# communication_module_to_aj-doy.net
KiCad netlist of a schematic drawn in EAGLE
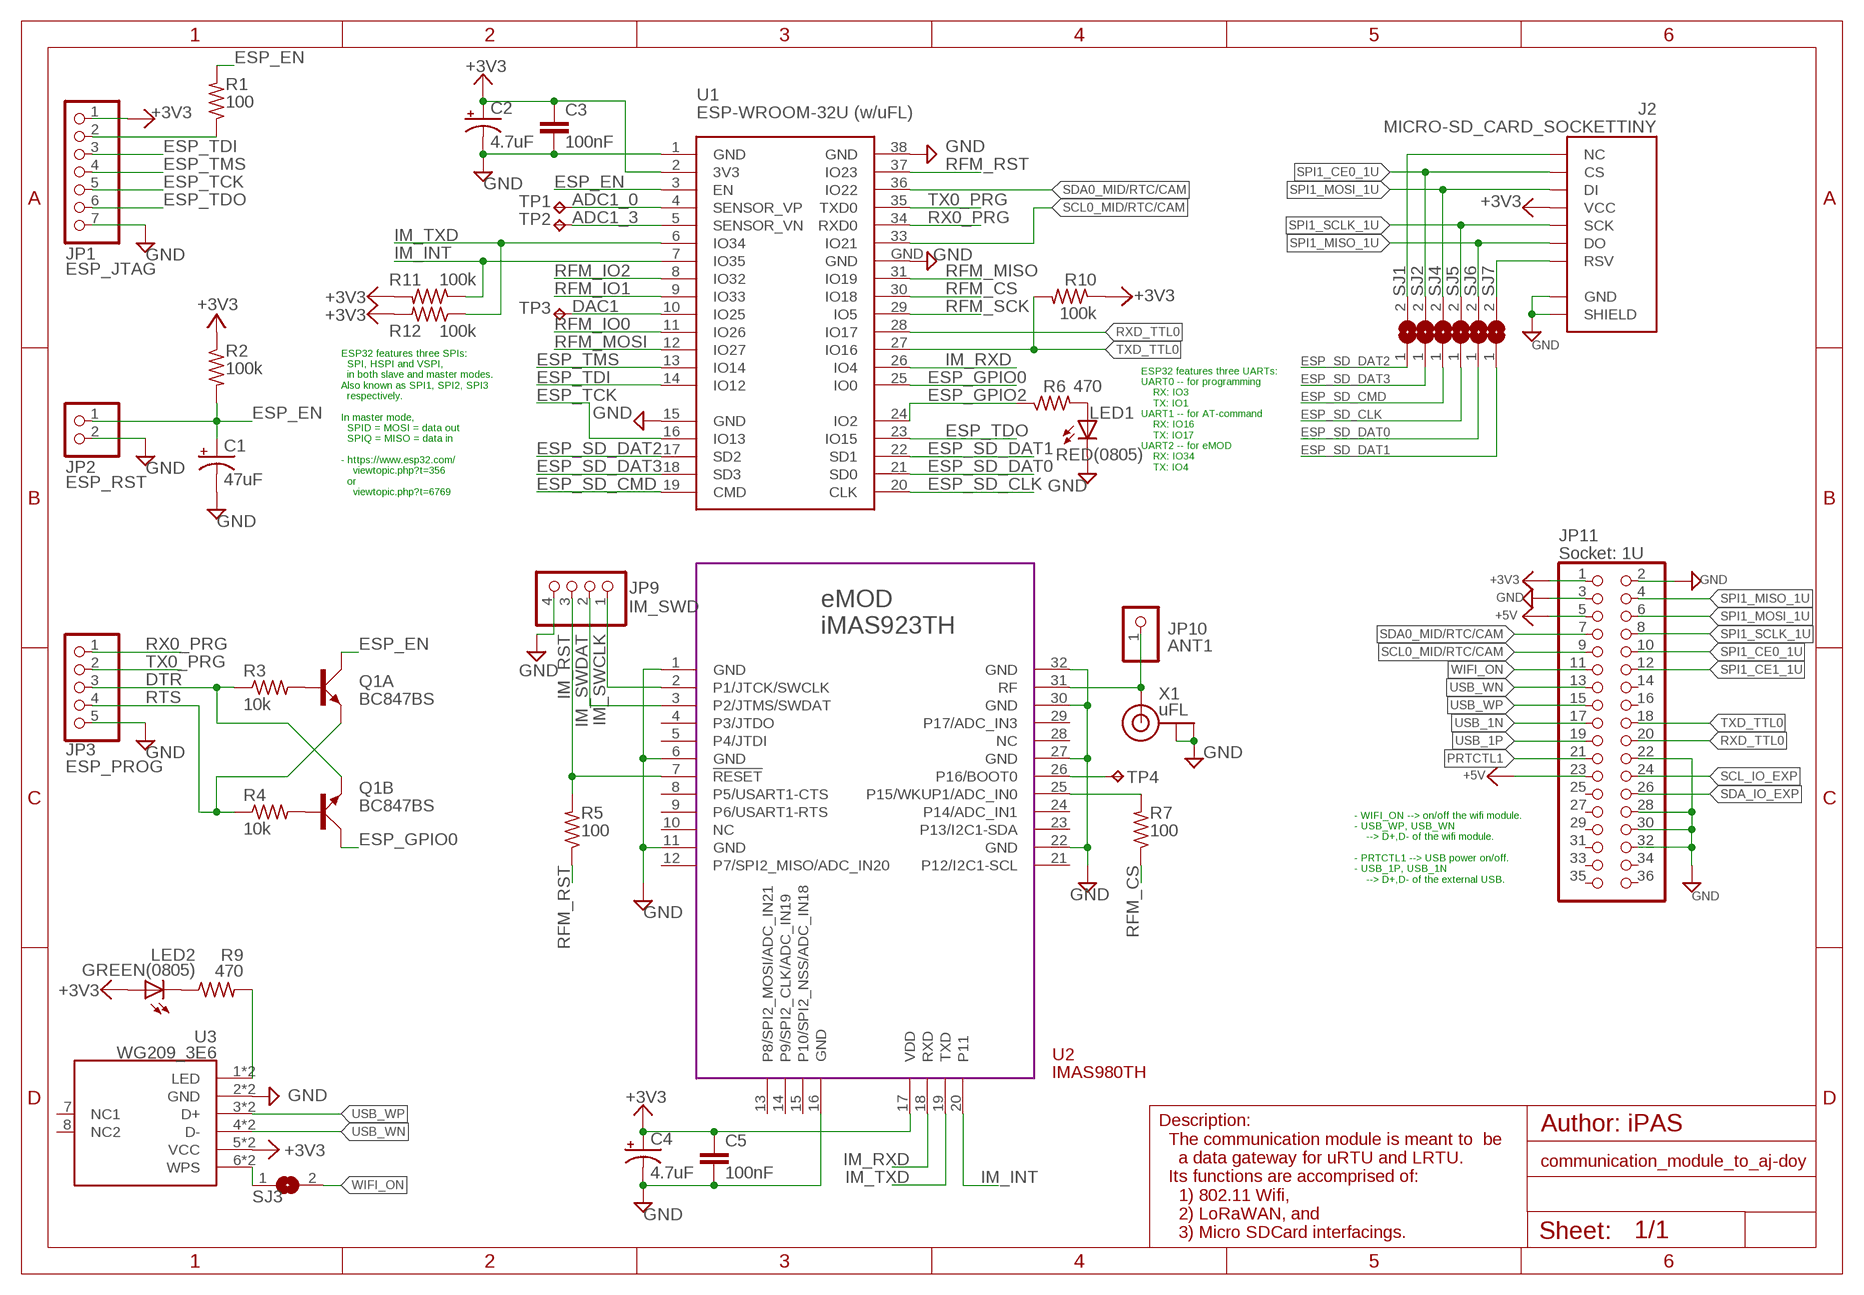
[diagram p0: schematic, sheet 1]

(export (version "E")
  (design (tool "Eeschema 10.0.6"))
  (components
    (comp (ref "C1")
      (value "47uF")
      (footprint "eagle-import:RCL_150CLZ-1014")
      (libsource (lib "eagle-import") (part "RCL_CPOL-US150CLZ-1014"))
    )
    (comp (ref "C2")
      (value "4.7uF")
      (footprint "eagle-import:RCL_150CLZ-1014")
      (libsource (lib "eagle-import") (part "RCL_CPOL-US150CLZ-1014"))
    )
    (comp (ref "C3")
      (value "100nF")
      (footprint "eagle-import:RCL_C1206")
      (libsource (lib "eagle-import") (part "RCL_C-EUC1206"))
    )
    (comp (ref "C4")
      (value "4.7uF")
      (footprint "eagle-import:RCL_150CLZ-1014")
      (libsource (lib "eagle-import") (part "RCL_CPOL-US150CLZ-1014"))
    )
    (comp (ref "C5")
      (value "100nF")
      (footprint "eagle-import:RCL_C1206")
      (libsource (lib "eagle-import") (part "RCL_C-EUC1206"))
    )
    (comp (ref "J2")
      (value "MICRO-SD_CARD_SOCKETTINY")
      (footprint "eagle-import:MICROSD_TINY")
      (libsource (lib "eagle-import") (part "MICRO-SD_CARD_SOCKETTINY"))
    )
    (comp (ref "JP1")
      (value "ESP_JTAG")
      (footprint "eagle-import:1X07")
      (libsource (lib "eagle-import") (part "PINHD-1X7"))
    )
    (comp (ref "JP2")
      (value "ESP_RST")
      (footprint "eagle-import:1X02")
      (libsource (lib "eagle-import") (part "PINHD-1X2"))
    )
    (comp (ref "JP3")
      (value "ESP_PROG")
      (footprint "eagle-import:1X05")
      (libsource (lib "eagle-import") (part "PINHD-1X5"))
    )
    (comp (ref "JP9")
      (value "IM_SWD")
      (footprint "eagle-import:1X04")
      (libsource (lib "eagle-import") (part "PINHD-1X4"))
    )
    (comp (ref "JP10")
      (value "ANT1")
      (footprint "eagle-import:1X01_ROUND")
      (libsource (lib "eagle-import") (part "HEADER-1X1ROUND"))
    )
    (comp (ref "JP11")
      (value "Socket: 1U")
      (footprint "eagle-import:2X18")
      (libsource (lib "eagle-import") (part "PINHD-2X18"))
    )
    (comp (ref "LED1")
      (value "RED(0805)")
      (footprint "eagle-import:CHIP-LED0805")
      (libsource (lib "eagle-import") (part "LEDCHIP-LED0805"))
    )
    (comp (ref "LED2")
      (value "GREEN(0805)")
      (footprint "eagle-import:CHIP-LED0805")
      (libsource (lib "eagle-import") (part "LEDCHIP-LED0805"))
    )
    (comp (ref "Q1")
      (value "BC847BS")
      (footprint "eagle-import:SOT363_PHILIPS")
      (libsource (lib "eagle-import") (part "BC847BS"))
    )
    (comp (ref "R1")
      (value "100")
      (footprint "eagle-import:RCL_M0805")
      (libsource (lib "eagle-import") (part "RCL_R-USM0805"))
    )
    (comp (ref "R2")
      (value "100k")
      (footprint "eagle-import:RCL_M0805")
      (libsource (lib "eagle-import") (part "RCL_R-USM0805"))
    )
    (comp (ref "R3")
      (value "10k")
      (footprint "eagle-import:RCL_M0805")
      (libsource (lib "eagle-import") (part "RCL_R-USM0805"))
    )
    (comp (ref "R4")
      (value "10k")
      (footprint "eagle-import:RCL_M0805")
      (libsource (lib "eagle-import") (part "RCL_R-USM0805"))
    )
    (comp (ref "R5")
      (value "100")
      (footprint "eagle-import:RCL_M0805")
      (libsource (lib "eagle-import") (part "RCL_R-USM0805"))
    )
    (comp (ref "R6")
      (value "470")
      (footprint "eagle-import:RCL_M0805")
      (libsource (lib "eagle-import") (part "RCL_R-USM0805"))
    )
    (comp (ref "R7")
      (value "100")
      (footprint "eagle-import:RCL_M0805")
      (libsource (lib "eagle-import") (part "RCL_R-USM0805"))
    )
    (comp (ref "R9")
      (value "470")
      (footprint "eagle-import:RCL_M0805")
      (libsource (lib "eagle-import") (part "RCL_R-USM0805"))
    )
    (comp (ref "R10")
      (value "100k")
      (footprint "eagle-import:RCL_M0805")
      (libsource (lib "eagle-import") (part "RCL_R-USM0805"))
    )
    (comp (ref "R11")
      (value "100k")
      (footprint "eagle-import:RCL_M0805")
      (libsource (lib "eagle-import") (part "RCL_R-USM0805"))
    )
    (comp (ref "R12")
      (value "100k")
      (footprint "eagle-import:RCL_M0805")
      (libsource (lib "eagle-import") (part "RCL_R-USM0805"))
    )
    (comp (ref "SJ1")
      (value "SOLDERJUMPERREFLOW")
      (footprint "eagle-import:SOLDERJUMPER_REFLOW")
      (libsource (lib "eagle-import") (part "SOLDERJUMPERREFLOW"))
    )
    (comp (ref "SJ2")
      (value "SOLDERJUMPERREFLOW")
      (footprint "eagle-import:SOLDERJUMPER_REFLOW")
      (libsource (lib "eagle-import") (part "SOLDERJUMPERREFLOW"))
    )
    (comp (ref "SJ3")
      (value "SOLDERJUMPERREFLOW")
      (footprint "eagle-import:SOLDERJUMPER_REFLOW")
      (libsource (lib "eagle-import") (part "SOLDERJUMPERREFLOW"))
    )
    (comp (ref "SJ4")
      (value "SOLDERJUMPERREFLOW")
      (footprint "eagle-import:SOLDERJUMPER_REFLOW")
      (libsource (lib "eagle-import") (part "SOLDERJUMPERREFLOW"))
    )
    (comp (ref "SJ5")
      (value "SOLDERJUMPERREFLOW")
      (footprint "eagle-import:SOLDERJUMPER_REFLOW")
      (libsource (lib "eagle-import") (part "SOLDERJUMPERREFLOW"))
    )
    (comp (ref "SJ6")
      (value "SOLDERJUMPERREFLOW")
      (footprint "eagle-import:SOLDERJUMPER_REFLOW")
      (libsource (lib "eagle-import") (part "SOLDERJUMPERREFLOW"))
    )
    (comp (ref "SJ7")
      (value "SOLDERJUMPERREFLOW")
      (footprint "eagle-import:SOLDERJUMPER_REFLOW")
      (libsource (lib "eagle-import") (part "SOLDERJUMPERREFLOW"))
    )
    (comp (ref "TP1")
      (value "TPB1,27")
      (footprint "eagle-import:B1,27")
      (libsource (lib "eagle-import") (part "TPB1,27"))
    )
    (comp (ref "TP2")
      (value "TPB1,27")
      (footprint "eagle-import:B1,27")
      (libsource (lib "eagle-import") (part "TPB1,27"))
    )
    (comp (ref "TP3")
      (value "TPB1,27")
      (footprint "eagle-import:B1,27")
      (libsource (lib "eagle-import") (part "TPB1,27"))
    )
    (comp (ref "TP4")
      (value "TPB1,27")
      (footprint "eagle-import:B1,27")
      (libsource (lib "eagle-import") (part "TPB1,27"))
    )
    (comp (ref "U1")
      (value "ESP-WROOM-32U (w/uFL)")
      (footprint "eagle-import:ESP-WROOM-32")
      (libsource (lib "eagle-import") (part "ESP-WROOM-32"))
    )
    (comp (ref "U2")
      (value "IMAS980TH")
      (footprint "eagle-import:IMAS923TH")
      (libsource (lib "eagle-import") (part "IMAS980TH"))
    )
    (comp (ref "U3")
      (value "WG209_3E6")
      (footprint "eagle-import:WG209")
      (libsource (lib "eagle-import") (part "WG209"))
    )
    (comp (ref "X1")
      (value "uFL")
      (footprint "eagle-import:U.FL")
      (libsource (lib "eagle-import") (part "ANTENNA_U.FL"))
    )
  )
  (nets
    (net (code "1") (name "+3V3") (class "Default")
      (node (ref "C2") (pin "+") (pinfunction "+_+") (pintype "passive"))
      (node (ref "C3") (pin "1") (pinfunction "1_1") (pintype "passive"))
      (node (ref "C4") (pin "+") (pinfunction "+_+") (pintype "passive"))
      (node (ref "C5") (pin "1") (pinfunction "1_1") (pintype "passive"))
      (node (ref "J2") (pin "4") (pinfunction "VCC_4") (pintype "bidirectional"))
      (node (ref "JP1") (pin "1") (pinfunction "1_1") (pintype "passive"))
      (node (ref "JP11") (pin "1") (pinfunction "1_1") (pintype "passive"))
      (node (ref "LED2") (pin "A") (pinfunction "A_A") (pintype "passive"))
      (node (ref "R10") (pin "1") (pinfunction "1_1") (pintype "passive"))
      (node (ref "R11") (pin "2") (pinfunction "2_2") (pintype "passive"))
      (node (ref "R12") (pin "2") (pinfunction "2_2") (pintype "passive"))
      (node (ref "R2") (pin "1") (pinfunction "1_1") (pintype "passive"))
      (node (ref "U1") (pin "2") (pinfunction "3V3_2") (pintype "power_in"))
      (node (ref "U2") (pin "17") (pinfunction "VDD_17") (pintype "power_in"))
      (node (ref "U3") (pin "5") (pinfunction "VCC_5") (pintype "power_in"))
      (node (ref "U3") (pin "5P") (pinfunction "VCC_5P") (pintype "power_in"))
    )
    (net (code "2") (name "+5V") (class "Default")
      (node (ref "JP11") (pin "23") (pinfunction "23_23") (pintype "passive"))
      (node (ref "JP11") (pin "5") (pinfunction "5_5") (pintype "passive"))
    )
    (net (code "3") (name "/ADC1_0") (class "Default")
      (node (ref "TP1") (pin "TP") (pinfunction "TP_TP") (pintype "input"))
      (node (ref "U1") (pin "4") (pinfunction "SENSOR_VP_4") (pintype "bidirectional"))
    )
    (net (code "4") (name "/ADC1_3") (class "Default")
      (node (ref "TP2") (pin "TP") (pinfunction "TP_TP") (pintype "input"))
      (node (ref "U1") (pin "5") (pinfunction "SENSOR_VN_5") (pintype "bidirectional"))
    )
    (net (code "5") (name "/DAC1") (class "Default")
      (node (ref "TP3") (pin "TP") (pinfunction "TP_TP") (pintype "input"))
      (node (ref "U1") (pin "10") (pinfunction "IO25_10") (pintype "bidirectional"))
    )
    (net (code "6") (name "/DTR") (class "Default")
      (node (ref "JP3") (pin "3") (pinfunction "3_3") (pintype "passive"))
      (node (ref "Q1") (pin "4") (pinfunction "E_4") (pintype "passive"))
      (node (ref "R3") (pin "1") (pinfunction "1_1") (pintype "passive"))
    )
    (net (code "7") (name "/ESP_EN") (class "Default")
      (node (ref "C1") (pin "+") (pinfunction "+_+") (pintype "passive"))
      (node (ref "JP2") (pin "1") (pinfunction "1_1") (pintype "passive"))
      (node (ref "Q1") (pin "6") (pinfunction "C_6") (pintype "passive"))
      (node (ref "R1") (pin "2") (pinfunction "2_2") (pintype "passive"))
      (node (ref "R2") (pin "2") (pinfunction "2_2") (pintype "passive"))
      (node (ref "U1") (pin "3") (pinfunction "EN_3") (pintype "input"))
    )
    (net (code "8") (name "/ESP_GPIO0") (class "Default")
      (node (ref "Q1") (pin "3") (pinfunction "C_3") (pintype "passive"))
      (node (ref "U1") (pin "25") (pinfunction "IO0_25") (pintype "bidirectional"))
    )
    (net (code "9") (name "/ESP_GPIO2") (class "Default")
      (node (ref "R6") (pin "1") (pinfunction "1_1") (pintype "passive"))
      (node (ref "U1") (pin "24") (pinfunction "IO2_24") (pintype "bidirectional"))
    )
    (net (code "10") (name "/ESP_SD_CLK") (class "Default")
      (node (ref "SJ5") (pin "1") (pinfunction "1_1") (pintype "passive"))
      (node (ref "U1") (pin "20") (pinfunction "CLK_20") (pintype "bidirectional"))
    )
    (net (code "11") (name "/ESP_SD_CMD") (class "Default")
      (node (ref "SJ4") (pin "1") (pinfunction "1_1") (pintype "passive"))
      (node (ref "U1") (pin "19") (pinfunction "CMD_19") (pintype "bidirectional"))
    )
    (net (code "12") (name "/ESP_SD_DAT0") (class "Default")
      (node (ref "SJ6") (pin "1") (pinfunction "1_1") (pintype "passive"))
      (node (ref "U1") (pin "21") (pinfunction "SD0_21") (pintype "bidirectional"))
    )
    (net (code "13") (name "/ESP_SD_DAT1") (class "Default")
      (node (ref "SJ7") (pin "1") (pinfunction "1_1") (pintype "passive"))
      (node (ref "U1") (pin "22") (pinfunction "SD1_22") (pintype "bidirectional"))
    )
    (net (code "14") (name "/ESP_SD_DAT2") (class "Default")
      (node (ref "SJ1") (pin "1") (pinfunction "1_1") (pintype "passive"))
      (node (ref "U1") (pin "17") (pinfunction "SD2_17") (pintype "bidirectional"))
    )
    (net (code "15") (name "/ESP_SD_DAT3") (class "Default")
      (node (ref "SJ2") (pin "1") (pinfunction "1_1") (pintype "passive"))
      (node (ref "U1") (pin "18") (pinfunction "SD3_18") (pintype "bidirectional"))
    )
    (net (code "16") (name "/ESP_TCK") (class "Default")
      (node (ref "JP1") (pin "5") (pinfunction "5_5") (pintype "passive"))
      (node (ref "U1") (pin "16") (pinfunction "IO13_16") (pintype "bidirectional"))
    )
    (net (code "17") (name "/ESP_TDI") (class "Default")
      (node (ref "JP1") (pin "3") (pinfunction "3_3") (pintype "passive"))
      (node (ref "U1") (pin "14") (pinfunction "IO12_14") (pintype "bidirectional"))
    )
    (net (code "18") (name "/ESP_TDO") (class "Default")
      (node (ref "JP1") (pin "6") (pinfunction "6_6") (pintype "passive"))
      (node (ref "U1") (pin "23") (pinfunction "IO15_23") (pintype "bidirectional"))
    )
    (net (code "19") (name "/ESP_TMS") (class "Default")
      (node (ref "JP1") (pin "4") (pinfunction "4_4") (pintype "passive"))
      (node (ref "U1") (pin "13") (pinfunction "IO14_13") (pintype "bidirectional"))
    )
    (net (code "20") (name "/IM_INT") (class "Default")
      (node (ref "R11") (pin "1") (pinfunction "1_1") (pintype "passive"))
      (node (ref "U1") (pin "7") (pinfunction "IO35_7") (pintype "bidirectional"))
      (node (ref "U2") (pin "20") (pinfunction "P11_20") (pintype "bidirectional"))
    )
    (net (code "21") (name "/IM_RST") (class "Default")
      (node (ref "JP9") (pin "3") (pinfunction "3_3") (pintype "passive"))
      (node (ref "R5") (pin "2") (pinfunction "2_2") (pintype "passive"))
      (node (ref "U2") (pin "7") (pinfunction "~{RESET}_7") (pintype "passive"))
    )
    (net (code "22") (name "/IM_RXD") (class "Default")
      (node (ref "U1") (pin "26") (pinfunction "IO4_26") (pintype "bidirectional"))
      (node (ref "U2") (pin "18") (pinfunction "RXD_18") (pintype "bidirectional"))
    )
    (net (code "23") (name "/IM_SWCLK") (class "Default")
      (node (ref "JP9") (pin "1") (pinfunction "1_1") (pintype "passive"))
      (node (ref "U2") (pin "2") (pinfunction "P1/JTCK/SWCLK_2") (pintype "bidirectional"))
    )
    (net (code "24") (name "/IM_SWDAT") (class "Default")
      (node (ref "JP9") (pin "2") (pinfunction "2_2") (pintype "passive"))
      (node (ref "U2") (pin "3") (pinfunction "P2/JTMS/SWDAT_3") (pintype "bidirectional"))
    )
    (net (code "25") (name "/IM_TXD") (class "Default")
      (node (ref "R12") (pin "1") (pinfunction "1_1") (pintype "passive"))
      (node (ref "U1") (pin "6") (pinfunction "IO34_6") (pintype "bidirectional"))
      (node (ref "U2") (pin "19") (pinfunction "TXD_19") (pintype "bidirectional"))
    )
    (net (code "26") (name "/RFM_CS") (class "Default")
      (node (ref "R7") (pin "1") (pinfunction "1_1") (pintype "passive"))
      (node (ref "U1") (pin "30") (pinfunction "IO18_30") (pintype "bidirectional"))
    )
    (net (code "27") (name "/RFM_IO0") (class "Default")
      (node (ref "U1") (pin "11") (pinfunction "IO26_11") (pintype "bidirectional"))
    )
    (net (code "28") (name "/RFM_IO1") (class "Default")
      (node (ref "U1") (pin "9") (pinfunction "IO33_9") (pintype "bidirectional"))
    )
    (net (code "29") (name "/RFM_IO2") (class "Default")
      (node (ref "U1") (pin "8") (pinfunction "IO32_8") (pintype "bidirectional"))
    )
    (net (code "30") (name "/RFM_MISO") (class "Default")
      (node (ref "U1") (pin "31") (pinfunction "IO19_31") (pintype "bidirectional"))
    )
    (net (code "31") (name "/RFM_MOSI") (class "Default")
      (node (ref "U1") (pin "12") (pinfunction "IO27_12") (pintype "bidirectional"))
    )
    (net (code "32") (name "/RFM_RST") (class "Default")
      (node (ref "R5") (pin "1") (pinfunction "1_1") (pintype "passive"))
      (node (ref "U1") (pin "37") (pinfunction "IO23_37") (pintype "bidirectional"))
    )
    (net (code "33") (name "/RFM_SCK") (class "Default")
      (node (ref "U1") (pin "29") (pinfunction "IO5_29") (pintype "bidirectional"))
    )
    (net (code "34") (name "/RTS") (class "Default")
      (node (ref "JP3") (pin "4") (pinfunction "4_4") (pintype "passive"))
      (node (ref "Q1") (pin "1") (pinfunction "E_1") (pintype "passive"))
      (node (ref "R4") (pin "1") (pinfunction "1_1") (pintype "passive"))
    )
    (net (code "35") (name "/RX0_PRG") (class "Default")
      (node (ref "JP3") (pin "1") (pinfunction "1_1") (pintype "passive"))
      (node (ref "U1") (pin "34") (pinfunction "RXD0_34") (pintype "bidirectional"))
    )
    (net (code "36") (name "/TX0_PRG") (class "Default")
      (node (ref "JP3") (pin "2") (pinfunction "2_2") (pintype "passive"))
      (node (ref "U1") (pin "35") (pinfunction "TXD0_35") (pintype "bidirectional"))
    )
    (net (code "37") (name "GND") (class "Default")
      (node (ref "C1") (pin "-") (pinfunction "-_-") (pintype "passive"))
      (node (ref "C2") (pin "-") (pinfunction "-_-") (pintype "passive"))
      (node (ref "C3") (pin "2") (pinfunction "2_2") (pintype "passive"))
      (node (ref "C4") (pin "-") (pinfunction "-_-") (pintype "passive"))
      (node (ref "C5") (pin "2") (pinfunction "2_2") (pintype "passive"))
      (node (ref "J2") (pin "6") (pinfunction "GND_6") (pintype "bidirectional"))
      (node (ref "J2") (pin "GND1") (pinfunction "SHIELD_GND1") (pintype "bidirectional"))
      (node (ref "J2") (pin "GND2") (pinfunction "SHIELD_GND2") (pintype "bidirectional"))
      (node (ref "J2") (pin "GND3") (pinfunction "SHIELD_GND3") (pintype "bidirectional"))
      (node (ref "J2") (pin "GND4") (pinfunction "SHIELD_GND4") (pintype "bidirectional"))
      (node (ref "J2") (pin "GND5") (pinfunction "SHIELD_GND5") (pintype "bidirectional"))
      (node (ref "J2") (pin "GND6") (pinfunction "SHIELD_GND6") (pintype "bidirectional"))
      (node (ref "JP1") (pin "7") (pinfunction "7_7") (pintype "passive"))
      (node (ref "JP11") (pin "2") (pinfunction "2_2") (pintype "passive"))
      (node (ref "JP11") (pin "22") (pinfunction "22_22") (pintype "passive"))
      (node (ref "JP11") (pin "28") (pinfunction "28_28") (pintype "passive"))
      (node (ref "JP11") (pin "3") (pinfunction "3_3") (pintype "passive"))
      (node (ref "JP11") (pin "30") (pinfunction "30_30") (pintype "passive"))
      (node (ref "JP11") (pin "32") (pinfunction "32_32") (pintype "passive"))
      (node (ref "JP2") (pin "2") (pinfunction "2_2") (pintype "passive"))
      (node (ref "JP3") (pin "5") (pinfunction "5_5") (pintype "passive"))
      (node (ref "JP9") (pin "4") (pinfunction "4_4") (pintype "passive"))
      (node (ref "LED1") (pin "C") (pinfunction "C_C") (pintype "passive"))
      (node (ref "U1") (pin "1") (pinfunction "GND_1") (pintype "power_in"))
      (node (ref "U1") (pin "15") (pinfunction "GND_15") (pintype "power_in"))
      (node (ref "U1") (pin "38") (pinfunction "GND_38") (pintype "power_in"))
      (node (ref "U1") (pin "GND") (pinfunction "GND_GND") (pintype "power_in"))
      (node (ref "U2") (pin "1") (pinfunction "GND_1") (pintype "power_in"))
      (node (ref "U2") (pin "11") (pinfunction "GND_11") (pintype "power_in"))
      (node (ref "U2") (pin "16") (pinfunction "GND_16") (pintype "power_in"))
      (node (ref "U2") (pin "22") (pinfunction "GND_22") (pintype "power_in"))
      (node (ref "U2") (pin "27") (pinfunction "GND_27") (pintype "power_in"))
      (node (ref "U2") (pin "30") (pinfunction "GND_30") (pintype "power_in"))
      (node (ref "U2") (pin "32") (pinfunction "GND_32") (pintype "power_in"))
      (node (ref "U2") (pin "6") (pinfunction "GND_6") (pintype "power_in"))
      (node (ref "U3") (pin "2") (pinfunction "GND_2") (pintype "power_in"))
      (node (ref "U3") (pin "2P") (pinfunction "GND_2P") (pintype "power_in"))
      (node (ref "X1") (pin "1") (pinfunction "GND_1") (pintype "passive"))
      (node (ref "X1") (pin "2") (pinfunction "GND_2") (pintype "passive"))
    )
    (net (code "38") (name "Net-(J2-NC)") (class "Default")
      (node (ref "J2") (pin "9") (pinfunction "NC_9") (pintype "bidirectional"))
      (node (ref "SJ1") (pin "2") (pinfunction "2_2") (pintype "passive"))
    )
    (net (code "39") (name "Net-(J2-RSV-Pad1)") (class "Default")
      (node (ref "J2") (pin "1") (pinfunction "RSV_1") (pintype "bidirectional"))
      (node (ref "J2") (pin "8") (pinfunction "RSV_8") (pintype "bidirectional"))
      (node (ref "SJ7") (pin "2") (pinfunction "2_2") (pintype "passive"))
    )
    (net (code "40") (name "Net-(JP1-Pad2)") (class "Default")
      (node (ref "JP1") (pin "2") (pinfunction "2_2") (pintype "passive"))
      (node (ref "R1") (pin "1") (pinfunction "1_1") (pintype "passive"))
    )
    (net (code "41") (name "Net-(LED1-PadA)") (class "Default")
      (node (ref "LED1") (pin "A") (pinfunction "A_A") (pintype "passive"))
      (node (ref "R6") (pin "2") (pinfunction "2_2") (pintype "passive"))
    )
    (net (code "42") (name "Net-(LED2-PadC)") (class "Default")
      (node (ref "LED2") (pin "C") (pinfunction "C_C") (pintype "passive"))
      (node (ref "R9") (pin "1") (pinfunction "1_1") (pintype "passive"))
    )
    (net (code "43") (name "Net-(Q1A-B)") (class "Default")
      (node (ref "Q1") (pin "2") (pinfunction "B_2") (pintype "passive"))
      (node (ref "R3") (pin "2") (pinfunction "2_2") (pintype "passive"))
    )
    (net (code "44") (name "Net-(Q1B-B)") (class "Default")
      (node (ref "Q1") (pin "5") (pinfunction "B_5") (pintype "passive"))
      (node (ref "R4") (pin "2") (pinfunction "2_2") (pintype "passive"))
    )
    (net (code "45") (name "Net-(R9-Pad2)") (class "Default")
      (node (ref "R9") (pin "2") (pinfunction "2_2") (pintype "passive"))
      (node (ref "U3") (pin "1") (pinfunction "LED_1") (pintype "bidirectional"))
      (node (ref "U3") (pin "1P") (pinfunction "LED_1P") (pintype "bidirectional"))
    )
    (net (code "46") (name "Net-(SJ3-Pad1)") (class "Default")
      (node (ref "SJ3") (pin "1") (pinfunction "1_1") (pintype "passive"))
      (node (ref "U3") (pin "6") (pinfunction "WPS_6") (pintype "bidirectional"))
      (node (ref "U3") (pin "6P") (pinfunction "WPS_6P") (pintype "bidirectional"))
    )
    (net (code "47") (name "Net-(U2-P15{slash}WKUP1{slash}ADC_IN0)") (class "Default")
      (node (ref "R7") (pin "2") (pinfunction "2_2") (pintype "passive"))
      (node (ref "U2") (pin "25") (pinfunction "P15/WKUP1/ADC_IN0_25") (pintype "bidirectional"))
    )
    (net (code "48") (name "Net-(U2-P16{slash}BOOT0)") (class "Default")
      (node (ref "TP4") (pin "TP") (pinfunction "TP_TP") (pintype "input"))
      (node (ref "U2") (pin "26") (pinfunction "P16/BOOT0_26") (pintype "passive"))
    )
    (net (code "49") (name "Net-(U2-RF)") (class "Default")
      (node (ref "JP10") (pin "1") (pinfunction "1_1") (pintype "passive"))
      (node (ref "U2") (pin "31") (pinfunction "RF_31") (pintype "bidirectional"))
      (node (ref "X1") (pin "3") (pinfunction "SIGNAL_3") (pintype "passive"))
    )
    (net (code "50") (name "PRTCTL1") (class "Default")
      (node (ref "JP11") (pin "21") (pinfunction "21_21") (pintype "passive"))
    )
    (net (code "51") (name "RXD_TTL0") (class "Default")
      (node (ref "JP11") (pin "20") (pinfunction "20_20") (pintype "passive"))
      (node (ref "U1") (pin "28") (pinfunction "IO17_28") (pintype "bidirectional"))
    )
    (net (code "52") (name "SCL0_MID{slash}RTC{slash}CAM") (class "Default")
      (node (ref "JP11") (pin "9") (pinfunction "9_9") (pintype "passive"))
      (node (ref "U1") (pin "33") (pinfunction "IO21_33") (pintype "bidirectional"))
    )
    (net (code "53") (name "SCL_IO_EXP") (class "Default")
      (node (ref "JP11") (pin "24") (pinfunction "24_24") (pintype "passive"))
    )
    (net (code "54") (name "SDA0_MID{slash}RTC{slash}CAM") (class "Default")
      (node (ref "JP11") (pin "7") (pinfunction "7_7") (pintype "passive"))
      (node (ref "U1") (pin "36") (pinfunction "IO22_36") (pintype "bidirectional"))
    )
    (net (code "55") (name "SDA_IO_EXP") (class "Default")
      (node (ref "JP11") (pin "26") (pinfunction "26_26") (pintype "passive"))
    )
    (net (code "56") (name "SPI1_CE0_1U") (class "Default")
      (node (ref "J2") (pin "2") (pinfunction "CS_2") (pintype "bidirectional"))
      (node (ref "JP11") (pin "10") (pinfunction "10_10") (pintype "passive"))
      (node (ref "SJ2") (pin "2") (pinfunction "2_2") (pintype "passive"))
    )
    (net (code "57") (name "SPI1_CE1_1U") (class "Default")
      (node (ref "JP11") (pin "12") (pinfunction "12_12") (pintype "passive"))
    )
    (net (code "58") (name "SPI1_MISO_1U") (class "Default")
      (node (ref "J2") (pin "7") (pinfunction "DO_7") (pintype "bidirectional"))
      (node (ref "JP11") (pin "4") (pinfunction "4_4") (pintype "passive"))
      (node (ref "SJ6") (pin "2") (pinfunction "2_2") (pintype "passive"))
    )
    (net (code "59") (name "SPI1_MOSI_1U") (class "Default")
      (node (ref "J2") (pin "3") (pinfunction "DI_3") (pintype "bidirectional"))
      (node (ref "JP11") (pin "6") (pinfunction "6_6") (pintype "passive"))
      (node (ref "SJ4") (pin "2") (pinfunction "2_2") (pintype "passive"))
    )
    (net (code "60") (name "SPI1_SCLK_1U") (class "Default")
      (node (ref "J2") (pin "5") (pinfunction "SCK_5") (pintype "bidirectional"))
      (node (ref "JP11") (pin "8") (pinfunction "8_8") (pintype "passive"))
      (node (ref "SJ5") (pin "2") (pinfunction "2_2") (pintype "passive"))
    )
    (net (code "61") (name "TXD_TTL0") (class "Default")
      (node (ref "JP11") (pin "18") (pinfunction "18_18") (pintype "passive"))
      (node (ref "R10") (pin "2") (pinfunction "2_2") (pintype "passive"))
      (node (ref "U1") (pin "27") (pinfunction "IO16_27") (pintype "bidirectional"))
    )
    (net (code "62") (name "USB_1N") (class "Default")
      (node (ref "JP11") (pin "17") (pinfunction "17_17") (pintype "passive"))
    )
    (net (code "63") (name "USB_1P") (class "Default")
      (node (ref "JP11") (pin "19") (pinfunction "19_19") (pintype "passive"))
    )
    (net (code "64") (name "USB_WN") (class "Default")
      (node (ref "JP11") (pin "13") (pinfunction "13_13") (pintype "passive"))
      (node (ref "U3") (pin "4") (pinfunction "D-_4") (pintype "bidirectional"))
      (node (ref "U3") (pin "4P") (pinfunction "D-_4P") (pintype "bidirectional"))
    )
    (net (code "65") (name "USB_WP") (class "Default")
      (node (ref "JP11") (pin "15") (pinfunction "15_15") (pintype "passive"))
      (node (ref "U3") (pin "3") (pinfunction "D+_3") (pintype "bidirectional"))
      (node (ref "U3") (pin "3P") (pinfunction "D+_3P") (pintype "bidirectional"))
    )
    (net (code "66") (name "WIFI_ON") (class "Default")
      (node (ref "JP11") (pin "11") (pinfunction "11_11") (pintype "passive"))
      (node (ref "SJ3") (pin "2") (pinfunction "2_2") (pintype "passive"))
    )
    (net (code "67") (name "unconnected-(JP11-Pad14)") (class "Default")
      (node (ref "JP11") (pin "14") (pinfunction "14_14") (pintype "passive"))
    )
    (net (code "68") (name "unconnected-(JP11-Pad16)") (class "Default")
      (node (ref "JP11") (pin "16") (pinfunction "16_16") (pintype "passive"))
    )
    (net (code "69") (name "unconnected-(JP11-Pad25)") (class "Default")
      (node (ref "JP11") (pin "25") (pinfunction "25_25") (pintype "passive"))
    )
    (net (code "70") (name "unconnected-(JP11-Pad27)") (class "Default")
      (node (ref "JP11") (pin "27") (pinfunction "27_27") (pintype "passive"))
    )
    (net (code "71") (name "unconnected-(JP11-Pad29)") (class "Default")
      (node (ref "JP11") (pin "29") (pinfunction "29_29") (pintype "passive"))
    )
    (net (code "72") (name "unconnected-(JP11-Pad31)") (class "Default")
      (node (ref "JP11") (pin "31") (pinfunction "31_31") (pintype "passive"))
    )
    (net (code "73") (name "unconnected-(JP11-Pad33)") (class "Default")
      (node (ref "JP11") (pin "33") (pinfunction "33_33") (pintype "passive"))
    )
    (net (code "74") (name "unconnected-(JP11-Pad34)") (class "Default")
      (node (ref "JP11") (pin "34") (pinfunction "34_34") (pintype "passive"))
    )
    (net (code "75") (name "unconnected-(JP11-Pad35)") (class "Default")
      (node (ref "JP11") (pin "35") (pinfunction "35_35") (pintype "passive"))
    )
    (net (code "76") (name "unconnected-(JP11-Pad36)") (class "Default")
      (node (ref "JP11") (pin "36") (pinfunction "36_36") (pintype "passive"))
    )
    (net (code "77") (name "unconnected-(U2-NC-Pad10)") (class "Default")
      (node (ref "U2") (pin "10") (pinfunction "NC_10") (pintype "no_connect"))
    )
    (net (code "78") (name "unconnected-(U2-NC-Pad28)") (class "Default")
      (node (ref "U2") (pin "28") (pinfunction "NC_28") (pintype "no_connect"))
    )
    (net (code "79") (name "unconnected-(U2-P3{slash}JTDO-Pad4)") (class "Default")
      (node (ref "U2") (pin "4") (pinfunction "P3/JTDO_4") (pintype "bidirectional"))
    )
    (net (code "80") (name "unconnected-(U2-P4{slash}JTDI-Pad5)") (class "Default")
      (node (ref "U2") (pin "5") (pinfunction "P4/JTDI_5") (pintype "bidirectional"))
    )
    (net (code "81") (name "unconnected-(U2-P5{slash}USART1-CTS-Pad8)") (class "Default")
      (node (ref "U2") (pin "8") (pinfunction "P5/USART1-CTS_8") (pintype "bidirectional"))
    )
    (net (code "82") (name "unconnected-(U2-P6{slash}USART1-RTS-Pad9)") (class "Default")
      (node (ref "U2") (pin "9") (pinfunction "P6/USART1-RTS_9") (pintype "bidirectional"))
    )
    (net (code "83") (name "unconnected-(U2-P7{slash}SPI2_MISO{slash}ADC_IN20-Pad12)") (class "Default")
      (node (ref "U2") (pin "12") (pinfunction "P7/SPI2_MISO/ADC_IN20_12") (pintype "bidirectional"))
    )
    (net (code "84") (name "unconnected-(U2-P8{slash}SPI2_MOSI{slash}ADC_IN21-Pad13)") (class "Default")
      (node (ref "U2") (pin "13") (pinfunction "P8/SPI2_MOSI/ADC_IN21_13") (pintype "bidirectional"))
    )
    (net (code "85") (name "unconnected-(U2-P9{slash}SPI2_CLK{slash}ADC_IN19-Pad14)") (class "Default")
      (node (ref "U2") (pin "14") (pinfunction "P9/SPI2_CLK/ADC_IN19_14") (pintype "bidirectional"))
    )
    (net (code "86") (name "unconnected-(U2-P10{slash}SPI2_NSS{slash}ADC_IN18-Pad15)") (class "Default")
      (node (ref "U2") (pin "15") (pinfunction "P10/SPI2_NSS/ADC_IN18_15") (pintype "bidirectional"))
    )
    (net (code "87") (name "unconnected-(U2-P12{slash}I2C1-SCL-Pad21)") (class "Default")
      (node (ref "U2") (pin "21") (pinfunction "P12/I2C1-SCL_21") (pintype "bidirectional"))
    )
    (net (code "88") (name "unconnected-(U2-P13{slash}I2C1-SDA-Pad23)") (class "Default")
      (node (ref "U2") (pin "23") (pinfunction "P13/I2C1-SDA_23") (pintype "bidirectional"))
    )
    (net (code "89") (name "unconnected-(U2-P14{slash}ADC_IN1-Pad24)") (class "Default")
      (node (ref "U2") (pin "24") (pinfunction "P14/ADC_IN1_24") (pintype "bidirectional"))
    )
    (net (code "90") (name "unconnected-(U2-P17{slash}ADC_IN3-Pad29)") (class "Default")
      (node (ref "U2") (pin "29") (pinfunction "P17/ADC_IN3_29") (pintype "bidirectional"))
    )
    (net (code "91") (name "unconnected-(U3-NC1-Pad7)") (class "Default")
      (node (ref "U3") (pin "7") (pinfunction "NC1_7") (pintype "no_connect"))
    )
    (net (code "92") (name "unconnected-(U3-NC2-Pad8)") (class "Default")
      (node (ref "U3") (pin "8") (pinfunction "NC2_8") (pintype "no_connect"))
    )
  )
)
